# Analog_Electronics_Fundamentals_103_-_La.net
KiCad netlist of a schematic drawn in EAGLE
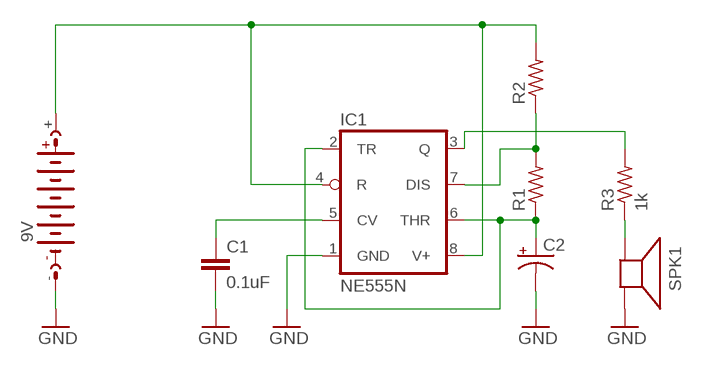
[diagram p0: schematic, sheet 1]

(export (version "E")
  (design (tool "Eeschema 10.0.6"))
  (components
    (comp (ref "9V")
      (value "AB9V")
      (footprint "eagle-import:AB9V")
      (libsource (lib "eagle-import") (part "AB9V"))
    )
    (comp (ref "C1")
      (value "0.1uF")
      (footprint "eagle-import:C025-024X044")
      (libsource (lib "eagle-import") (part "C-EU025-024X044"))
    )
    (comp (ref "C2")
      (value "CPOL-USTT5D11")
      (footprint "eagle-import:TT5D11")
      (libsource (lib "eagle-import") (part "CPOL-USTT5D11"))
    )
    (comp (ref "IC1")
      (value "NE555N")
      (footprint "eagle-import:DIL08")
      (libsource (lib "eagle-import") (part "555NNE"))
    )
    (comp (ref "R1")
      (value "R-US_0204/7")
      (footprint "eagle-import:0204_7")
      (libsource (lib "eagle-import") (part "R-US_0204/7"))
    )
    (comp (ref "R2")
      (value "R-US_0204/7")
      (footprint "eagle-import:0204_7")
      (libsource (lib "eagle-import") (part "R-US_0204/7"))
    )
    (comp (ref "R3")
      (value "1k")
      (footprint "eagle-import:0204_7")
      (libsource (lib "eagle-import") (part "R-US_0204/7"))
    )
    (comp (ref "SPK1")
      (value "SMT-0540-S-R")
      (footprint "eagle-import:SMT-0540-S-R")
      (libsource (lib "eagle-import") (part "SMT-0540-S-R"))
    )
  )
  (nets
    (net (code "1") (name "GND") (class "Default")
      (node (ref "9V") (pin "-") (pinfunction "-_-") (pintype "passive"))
      (node (ref "C1") (pin "2") (pinfunction "2_2") (pintype "passive"))
      (node (ref "C2") (pin "-") (pinfunction "-_-") (pintype "passive"))
      (node (ref "IC1") (pin "1") (pinfunction "GND_1") (pintype "power_in"))
      (node (ref "SPK1") (pin "+") (pinfunction "-_+") (pintype "passive"))
    )
    (net (code "2") (name "Net-(IC1-CV)") (class "Default")
      (node (ref "C1") (pin "1") (pinfunction "1_1") (pintype "passive"))
      (node (ref "IC1") (pin "5") (pinfunction "CV_5") (pintype "input"))
    )
    (net (code "3") (name "Net-(IC1-DIS)") (class "Default")
      (node (ref "IC1") (pin "7") (pinfunction "DIS_7") (pintype "input"))
      (node (ref "R1") (pin "2") (pinfunction "2_2") (pintype "passive"))
      (node (ref "R2") (pin "1") (pinfunction "1_1") (pintype "passive"))
    )
    (net (code "4") (name "Net-(IC1-Q)") (class "Default")
      (node (ref "IC1") (pin "3") (pinfunction "Q_3") (pintype "output"))
      (node (ref "R3") (pin "2") (pinfunction "2_2") (pintype "passive"))
    )
    (net (code "5") (name "Net-(IC1-R)") (class "Default")
      (node (ref "9V") (pin "+") (pinfunction "+_+") (pintype "passive"))
      (node (ref "IC1") (pin "4") (pinfunction "R_4") (pintype "input"))
      (node (ref "IC1") (pin "8") (pinfunction "V+_8") (pintype "power_in"))
      (node (ref "R2") (pin "2") (pinfunction "2_2") (pintype "passive"))
    )
    (net (code "6") (name "Net-(IC1-THR)") (class "Default")
      (node (ref "C2") (pin "+") (pinfunction "+_+") (pintype "passive"))
      (node (ref "IC1") (pin "2") (pinfunction "TR_2") (pintype "input"))
      (node (ref "IC1") (pin "6") (pinfunction "THR_6") (pintype "input"))
      (node (ref "R1") (pin "1") (pinfunction "1_1") (pintype "passive"))
    )
    (net (code "7") (name "Net-(SPK1-+)") (class "Default")
      (node (ref "R3") (pin "1") (pinfunction "1_1") (pintype "passive"))
      (node (ref "SPK1") (pin "-") (pinfunction "+_-") (pintype "passive"))
    )
  )
)
